# SparkFun_RF_Transceiver-RFM22B.net
KiCad netlist of a schematic drawn in EAGLE
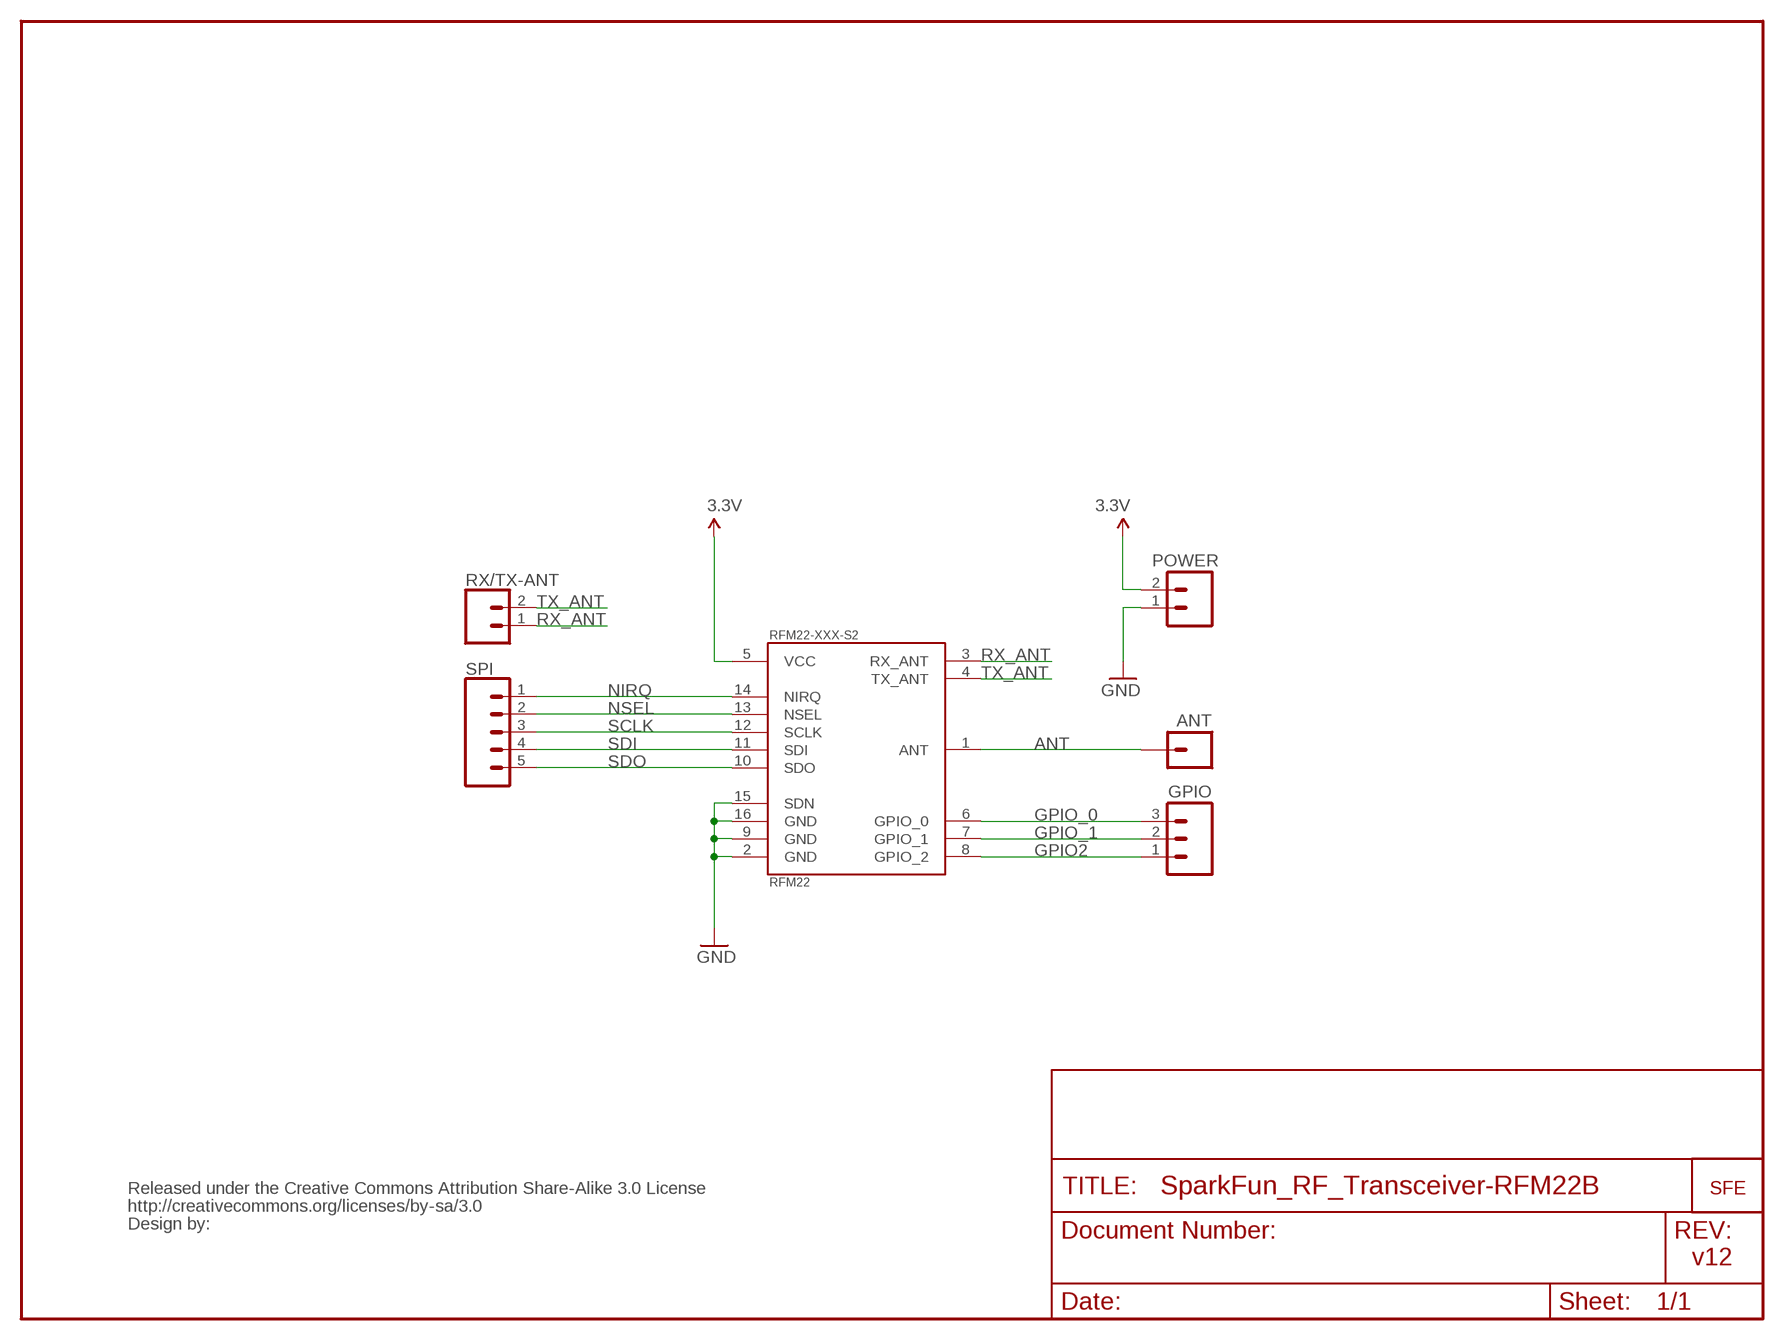
[diagram p0: schematic, sheet 1]

(export (version "E")
  (design (tool "Eeschema 10.0.6"))
  (components
    (comp (ref "JP0")
      (value "POWER")
      (footprint "eagle-import:1X02")
      (libsource (lib "eagle-import") (part "M02PTH"))
    )
    (comp (ref "JP1")
      (value "LOGO-SFENEW")
      (footprint "eagle-import:SFE-NEW-WEBLOGO")
      (libsource (lib "eagle-import") (part "LOGO-SFENEW"))
    )
    (comp (ref "JP2")
      (value "ANT")
      (footprint "eagle-import:1X01")
      (libsource (lib "eagle-import") (part "M01PTH"))
    )
    (comp (ref "JP3")
      (value "GPIO")
      (footprint "eagle-import:1X03")
      (libsource (lib "eagle-import") (part "M03PTH"))
    )
    (comp (ref "JP4")
      (value "SPI")
      (footprint "eagle-import:1X05")
      (libsource (lib "eagle-import") (part "M05PTH"))
    )
    (comp (ref "JP5")
      (value "RX/TX-ANT")
      (footprint "eagle-import:1X02")
      (libsource (lib "eagle-import") (part "M02PTH"))
    )
    (comp (ref "RFM22-XXX-S2")
      (value "RFM22")
      (footprint "eagle-import:RFM22-XXX-S2")
      (libsource (lib "eagle-import") (part "RFM22"))
    )
    (comp (ref "U$1")
      (value "CREATIVE_COMMONS")
      (footprint "eagle-import:CREATIVE_COMMONS")
      (libsource (lib "eagle-import") (part "CREATIVE_COMMONS"))
    )
  )
  (nets
    (net (code "1") (name "/ANT") (class "Default")
      (node (ref "JP2") (pin "1") (pinfunction "1_1") (pintype "passive"))
      (node (ref "RFM22-XXX-S2") (pin "1") (pinfunction "ANT_1") (pintype "bidirectional"))
    )
    (net (code "2") (name "/GPIO2") (class "Default")
      (node (ref "JP3") (pin "1") (pinfunction "1_1") (pintype "passive"))
      (node (ref "RFM22-XXX-S2") (pin "8") (pinfunction "GPIO_2_8") (pintype "bidirectional"))
    )
    (net (code "3") (name "/GPIO_0") (class "Default")
      (node (ref "JP3") (pin "3") (pinfunction "3_3") (pintype "passive"))
      (node (ref "RFM22-XXX-S2") (pin "6") (pinfunction "GPIO_0_6") (pintype "bidirectional"))
    )
    (net (code "4") (name "/GPIO_1") (class "Default")
      (node (ref "JP3") (pin "2") (pinfunction "2_2") (pintype "passive"))
      (node (ref "RFM22-XXX-S2") (pin "7") (pinfunction "GPIO_1_7") (pintype "bidirectional"))
    )
    (net (code "5") (name "/NIRQ") (class "Default")
      (node (ref "JP4") (pin "1") (pinfunction "1_1") (pintype "passive"))
      (node (ref "RFM22-XXX-S2") (pin "14") (pinfunction "NIRQ_14") (pintype "output"))
    )
    (net (code "6") (name "/NSEL") (class "Default")
      (node (ref "JP4") (pin "2") (pinfunction "2_2") (pintype "passive"))
      (node (ref "RFM22-XXX-S2") (pin "13") (pinfunction "NSEL_13") (pintype "input"))
    )
    (net (code "7") (name "/RX_ANT") (class "Default")
      (node (ref "JP5") (pin "1") (pinfunction "1_1") (pintype "passive"))
      (node (ref "RFM22-XXX-S2") (pin "3") (pinfunction "RX_ANT_3") (pintype "input"))
    )
    (net (code "8") (name "/SCLK") (class "Default")
      (node (ref "JP4") (pin "3") (pinfunction "3_3") (pintype "passive"))
      (node (ref "RFM22-XXX-S2") (pin "12") (pinfunction "SCLK_12") (pintype "input"))
    )
    (net (code "9") (name "/SDI") (class "Default")
      (node (ref "JP4") (pin "4") (pinfunction "4_4") (pintype "passive"))
      (node (ref "RFM22-XXX-S2") (pin "11") (pinfunction "SDI_11") (pintype "input"))
    )
    (net (code "10") (name "/SDO") (class "Default")
      (node (ref "JP4") (pin "5") (pinfunction "5_5") (pintype "passive"))
      (node (ref "RFM22-XXX-S2") (pin "10") (pinfunction "SDO_10") (pintype "output"))
    )
    (net (code "11") (name "/TX_ANT") (class "Default")
      (node (ref "JP5") (pin "2") (pinfunction "2_2") (pintype "passive"))
      (node (ref "RFM22-XXX-S2") (pin "4") (pinfunction "TX_ANT_4") (pintype "input"))
    )
    (net (code "12") (name "3.3V") (class "Default")
      (node (ref "JP0") (pin "2") (pinfunction "2_2") (pintype "passive"))
      (node (ref "RFM22-XXX-S2") (pin "5") (pinfunction "VCC_5") (pintype "bidirectional"))
    )
    (net (code "13") (name "GND") (class "Default")
      (node (ref "JP0") (pin "1") (pinfunction "1_1") (pintype "passive"))
      (node (ref "RFM22-XXX-S2") (pin "15") (pinfunction "SDN_15") (pintype "input"))
      (node (ref "RFM22-XXX-S2") (pin "16") (pinfunction "GND_16") (pintype "power_in"))
      (node (ref "RFM22-XXX-S2") (pin "2") (pinfunction "GND_2") (pintype "power_in"))
      (node (ref "RFM22-XXX-S2") (pin "9") (pinfunction "GND_9") (pintype "power_in"))
    )
  )
)
